# SZG-TEMPLATE-STD.net
KiCad netlist of a schematic drawn in Altium Designer
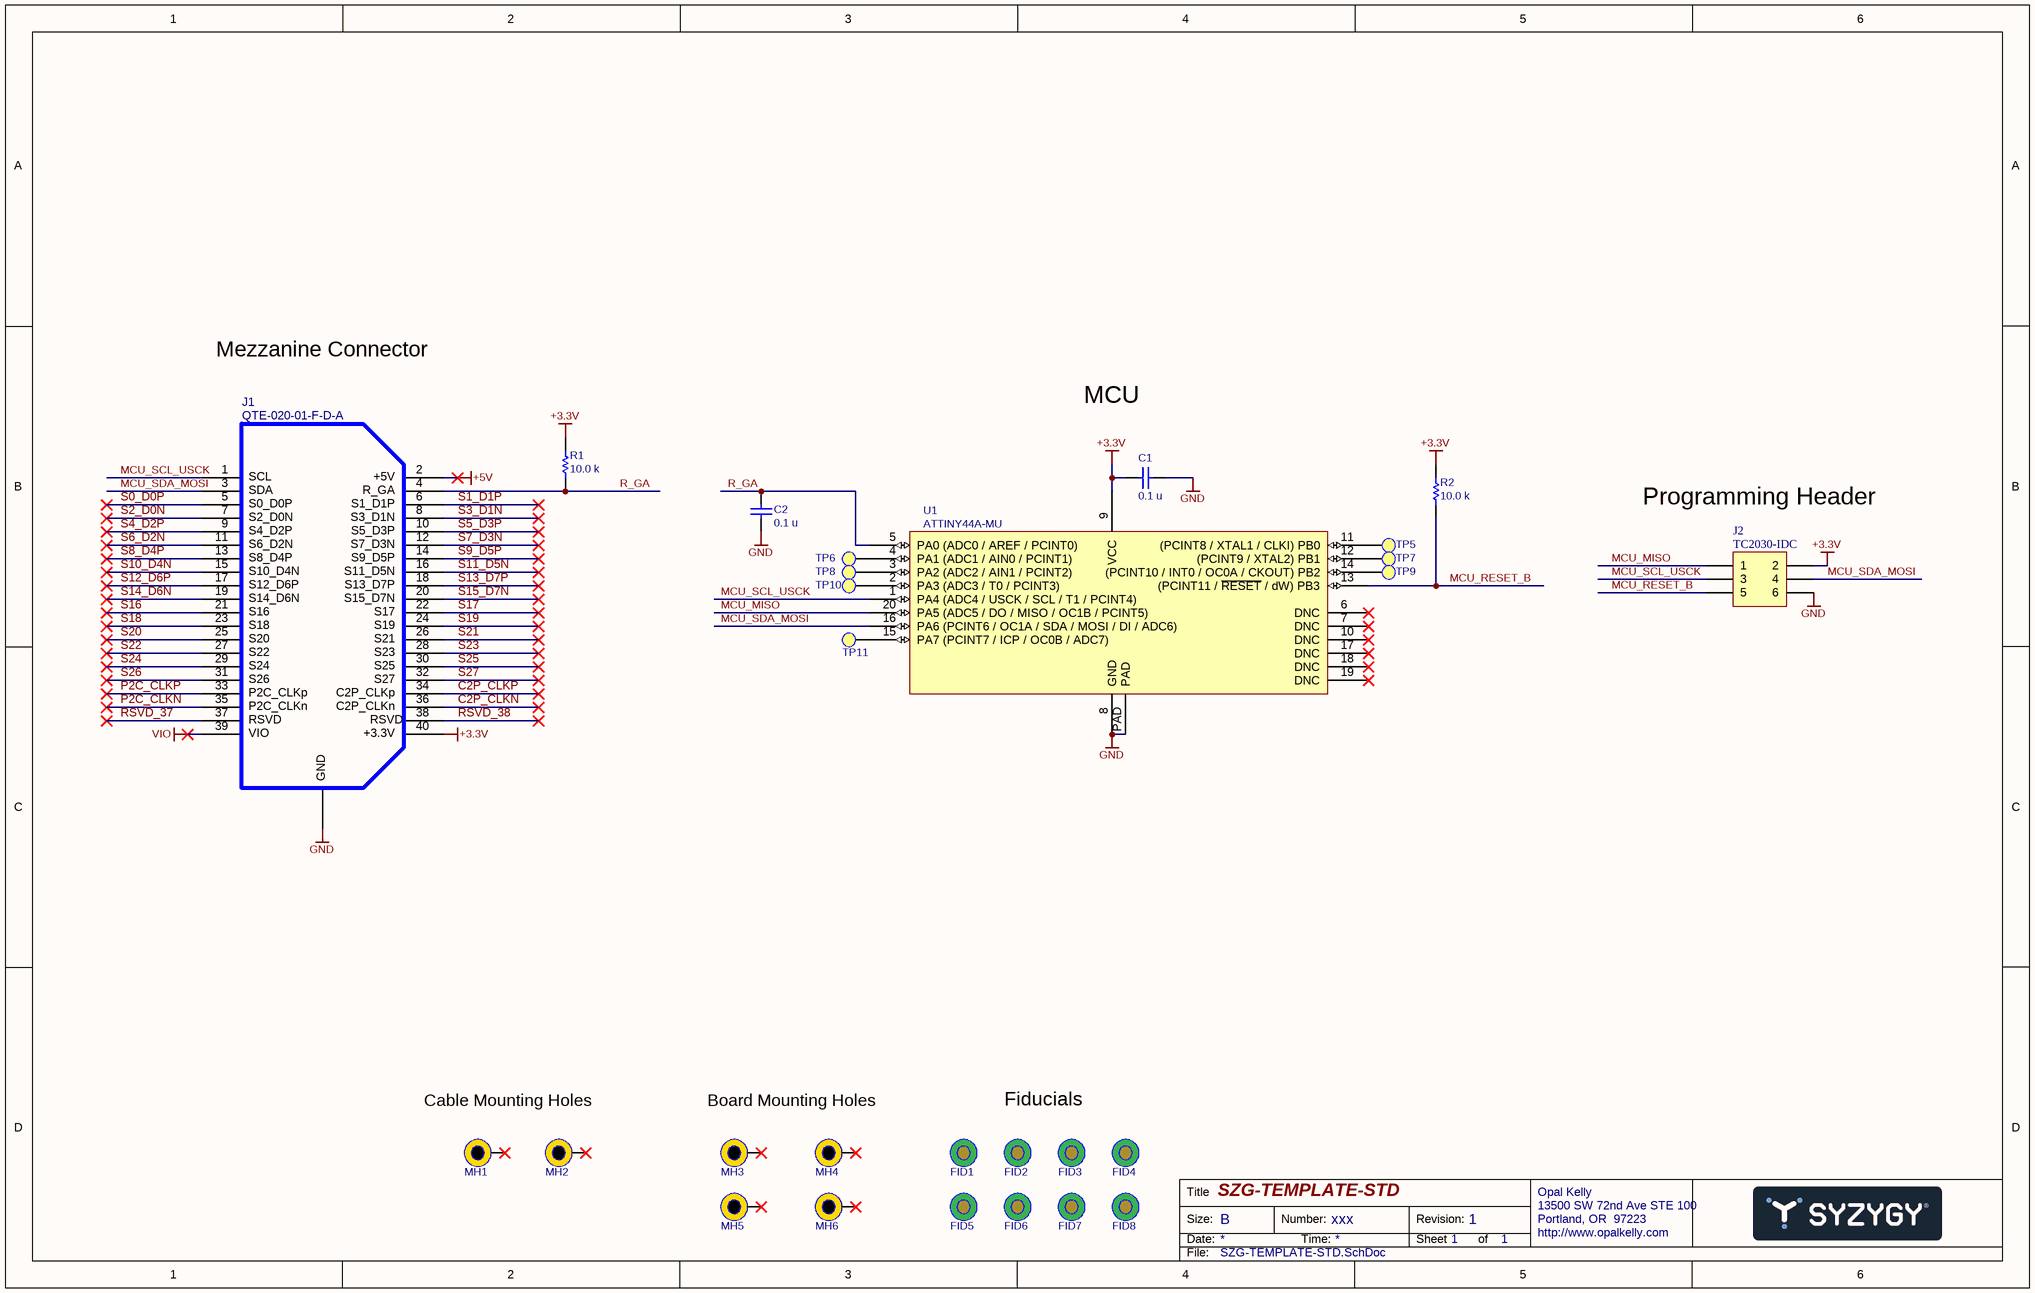
[diagram p0: SZG-TEMPLATE-STD.SchDoc]

(export (version "E")
  (design (tool "Eeschema 10.0.6"))
  (components
    (comp (ref "C1")
      (value "0.1 u")
      (footprint "CAPC1005X06N")
      (description "Ceramic capacitor")
      (fields (field (name "MANUFACTURER") "Kemet") (field (name "PARTNUMBER") "000070"))
      (libsource (lib "Aligni") (part "Capacitor"))
    )
    (comp (ref "C2")
      (value "0.1 u")
      (footprint "CAPC1005X06N")
      (description "Ceramic capacitor")
      (fields (field (name "MANUFACTURER") "Kemet") (field (name "PARTNUMBER") "000070"))
      (libsource (lib "Aligni") (part "Capacitor"))
    )
    (comp (ref "FID1")
      (value "FIDUCIAL")
      (footprint "FID1MM/2MM-SS")
      (description "PCB fiducial")
      (libsource (lib "NoBOM") (part "FIDUCIAL"))
    )
    (comp (ref "FID2")
      (value "FIDUCIAL")
      (footprint "FID1MM/2MM-SS")
      (description "PCB fiducial")
      (libsource (lib "NoBOM") (part "FIDUCIAL"))
    )
    (comp (ref "FID3")
      (value "FIDUCIAL")
      (footprint "FID1MM/2MM-SS")
      (description "PCB fiducial")
      (libsource (lib "NoBOM") (part "FIDUCIAL"))
    )
    (comp (ref "FID4")
      (value "FIDUCIAL")
      (footprint "FID1MM/2MM-SS")
      (description "PCB fiducial")
      (libsource (lib "NoBOM") (part "FIDUCIAL"))
    )
    (comp (ref "FID5")
      (value "FIDUCIAL")
      (footprint "FID1MM/2MM-SS")
      (description "PCB fiducial")
      (libsource (lib "NoBOM") (part "FIDUCIAL"))
    )
    (comp (ref "FID6")
      (value "FIDUCIAL")
      (footprint "FID1MM/2MM-SS")
      (description "PCB fiducial")
      (libsource (lib "NoBOM") (part "FIDUCIAL"))
    )
    (comp (ref "FID7")
      (value "FIDUCIAL")
      (footprint "FID1MM/2MM-SS")
      (description "PCB fiducial")
      (libsource (lib "NoBOM") (part "FIDUCIAL"))
    )
    (comp (ref "FID8")
      (value "FIDUCIAL")
      (footprint "FID1MM/2MM-SS")
      (description "PCB fiducial")
      (libsource (lib "NoBOM") (part "FIDUCIAL"))
    )
    (comp (ref "J1")
      (value "QTE-020-01-F-D-A")
      (footprint "QTE-020-01-X-D-A-L")
      (fields (field (name "PARTNUMBER") "000973") (field (name "MANUFACTURER") "Samtec"))
      (libsource (lib "Aligni") (part "QTE_QSE-020"))
    )
    (comp (ref "J2")
      (value "~")
      (footprint "TC2030-DUAL")
      (description "Tag-Connect 6-pin Plug-of-Nails spring-pin cable footprint")
      (fields
        (field (name "ALIGNIPARTNUMBER") "002062")
        (field (name "MANUFACTURER") "Tag-Connect")
        (field (name "MANUFACTURER_PN") "TC2030-IDC")
      )
      (libsource (lib "Aligni") (part "Header 3X2"))
    )
    (comp (ref "MH1")
      (value "MTG")
      (footprint "MTG-3.2/6.5-PTH")
      (description "Mounting hole")
      (libsource (lib "NoBOM") (part "MTG"))
    )
    (comp (ref "MH2")
      (value "MTG")
      (footprint "MTG-3.2/6.5-PTH")
      (description "Mounting hole")
      (libsource (lib "NoBOM") (part "MTG"))
    )
    (comp (ref "MH3")
      (value "MTG")
      (footprint "MTG-3.2/6.5-PTH")
      (description "Mounting hole")
      (libsource (lib "NoBOM") (part "MTG"))
    )
    (comp (ref "MH4")
      (value "MTG")
      (footprint "MTG-3.2/6.5-PTH")
      (description "Mounting hole")
      (libsource (lib "NoBOM") (part "MTG"))
    )
    (comp (ref "MH5")
      (value "MTG")
      (footprint "MTG-3.2/6.5-PTH")
      (description "Mounting hole")
      (libsource (lib "NoBOM") (part "MTG"))
    )
    (comp (ref "MH6")
      (value "MTG")
      (footprint "MTG-3.2/6.5-PTH")
      (description "Mounting hole")
      (libsource (lib "NoBOM") (part "MTG"))
    )
    (comp (ref "R1")
      (value "10.0 k")
      (footprint "RESC1005X06N")
      (description "Thick-film resistor")
      (fields (field (name "MANUFACTURER") "Vishay") (field (name "PARTNUMBER") "001521"))
      (libsource (lib "Aligni") (part "Resistor"))
    )
    (comp (ref "R2")
      (value "10.0 k")
      (footprint "RESC1005X06N")
      (description "Thick-film resistor")
      (fields (field (name "MANUFACTURER") "Vishay") (field (name "PARTNUMBER") "001521"))
      (libsource (lib "Aligni") (part "Resistor"))
    )
    (comp (ref "TP5")
      (value "TESTPOINT-SMD20")
      (footprint "TP-SMD20")
      (description "Test point, surface-mount, 20mil")
      (libsource (lib "NoBOM") (part "TESTPOINT-SMD20"))
    )
    (comp (ref "TP6")
      (value "TESTPOINT-SMD20")
      (footprint "TP-SMD20")
      (description "Test point, surface-mount, 20mil")
      (libsource (lib "NoBOM") (part "TESTPOINT-SMD20"))
    )
    (comp (ref "TP7")
      (value "TESTPOINT-SMD20")
      (footprint "TP-SMD20")
      (description "Test point, surface-mount, 20mil")
      (libsource (lib "NoBOM") (part "TESTPOINT-SMD20"))
    )
    (comp (ref "TP8")
      (value "TESTPOINT-SMD20")
      (footprint "TP-SMD20")
      (description "Test point, surface-mount, 20mil")
      (libsource (lib "NoBOM") (part "TESTPOINT-SMD20"))
    )
    (comp (ref "TP9")
      (value "TESTPOINT-SMD20")
      (footprint "TP-SMD20")
      (description "Test point, surface-mount, 20mil")
      (libsource (lib "NoBOM") (part "TESTPOINT-SMD20"))
    )
    (comp (ref "TP10")
      (value "TESTPOINT-SMD20")
      (footprint "TP-SMD20")
      (description "Test point, surface-mount, 20mil")
      (libsource (lib "NoBOM") (part "TESTPOINT-SMD20"))
    )
    (comp (ref "TP11")
      (value "TESTPOINT-SMD20")
      (footprint "TP-SMD20")
      (description "Test point, surface-mount, 20mil")
      (libsource (lib "NoBOM") (part "TESTPOINT-SMD20"))
    )
    (comp (ref "U1")
      (value "ATTINY44A-MU")
      (footprint "QFN-EP-20")
      (description "8-bit MCU, 4 KB flash, 256 bytes EEPROM")
      (fields (field (name "MANUFACTURER") "Microchip") (field (name "PARTNUMBER") "001552"))
      (libsource (lib "Aligni") (part "ATTINYx4A-MU"))
    )
  )
  (nets
    (net (code "1") (name "+3.3V") (class "Default")
      (node (ref "C1") (pin "2") (pinfunction "2_2") (pintype "passive"))
      (node (ref "J1") (pin "40") (pinfunction "40_40") (pintype "passive"))
      (node (ref "J2") (pin "2") (pinfunction "2_2") (pintype "passive"))
      (node (ref "R1") (pin "2") (pinfunction "2_2") (pintype "passive"))
      (node (ref "R2") (pin "2") (pinfunction "2_2") (pintype "passive"))
      (node (ref "U1") (pin "9") (pinfunction "VCC_9") (pintype "power_in"))
    )
    (net (code "2") (name "+5V") (class "Default")
      (node (ref "J1") (pin "2") (pinfunction "2_2") (pintype "passive"))
    )
    (net (code "3") (name "/C2P_CLKN") (class "Default")
      (node (ref "J1") (pin "36") (pinfunction "36_36") (pintype "passive+no_connect"))
    )
    (net (code "4") (name "/C2P_CLKP") (class "Default")
      (node (ref "J1") (pin "34") (pinfunction "34_34") (pintype "passive+no_connect"))
    )
    (net (code "5") (name "/MCU_MISO") (class "Default")
      (node (ref "J2") (pin "1") (pinfunction "1_1") (pintype "passive"))
      (node (ref "U1") (pin "20") (pinfunction "PA5_(ADC5_/_DO_/_MISO_/_OC1B_/_PCINT5)_20") (pintype "bidirectional"))
    )
    (net (code "6") (name "/MCU_RESET_B") (class "Default")
      (node (ref "J2") (pin "5") (pinfunction "5_5") (pintype "passive"))
      (node (ref "R2") (pin "1") (pinfunction "1_1") (pintype "passive"))
      (node (ref "U1") (pin "13") (pinfunction "(PCINT11_/_~{RESET}_/_dW)_PB3_13") (pintype "bidirectional"))
    )
    (net (code "7") (name "/MCU_SCL_USCK") (class "Default")
      (node (ref "J1") (pin "1") (pinfunction "1_1") (pintype "passive"))
      (node (ref "J2") (pin "3") (pinfunction "3_3") (pintype "passive"))
      (node (ref "U1") (pin "1") (pinfunction "PA4_(ADC4_/_USCK_/_SCL_/_T1_/_PCINT4)_1") (pintype "bidirectional"))
    )
    (net (code "8") (name "/MCU_SDA_MOSI") (class "Default")
      (node (ref "J1") (pin "3") (pinfunction "3_3") (pintype "passive"))
      (node (ref "J2") (pin "4") (pinfunction "4_4") (pintype "passive"))
      (node (ref "U1") (pin "16") (pinfunction "PA6_(PCINT6_/_OC1A_/_SDA_/_MOSI_/_DI_/_ADC6)_16") (pintype "bidirectional"))
    )
    (net (code "9") (name "/P2C_CLKN") (class "Default")
      (node (ref "J1") (pin "35") (pinfunction "35_35") (pintype "passive+no_connect"))
    )
    (net (code "10") (name "/P2C_CLKP") (class "Default")
      (node (ref "J1") (pin "33") (pinfunction "33_33") (pintype "passive+no_connect"))
    )
    (net (code "11") (name "/RSVD_37") (class "Default")
      (node (ref "J1") (pin "37") (pinfunction "37_37") (pintype "passive+no_connect"))
    )
    (net (code "12") (name "/RSVD_38") (class "Default")
      (node (ref "J1") (pin "38") (pinfunction "38_38") (pintype "passive+no_connect"))
    )
    (net (code "13") (name "/R_GA") (class "Default")
      (node (ref "C2") (pin "2") (pinfunction "2_2") (pintype "passive"))
      (node (ref "J1") (pin "4") (pinfunction "4_4") (pintype "passive"))
      (node (ref "R1") (pin "1") (pinfunction "1_1") (pintype "passive"))
      (node (ref "U1") (pin "5") (pinfunction "PA0_(ADC0_/_AREF_/_PCINT0)_5") (pintype "bidirectional"))
    )
    (net (code "14") (name "/S0_D0P") (class "Default")
      (node (ref "J1") (pin "5") (pinfunction "5_5") (pintype "passive+no_connect"))
    )
    (net (code "15") (name "/S1_D1P") (class "Default")
      (node (ref "J1") (pin "6") (pinfunction "6_6") (pintype "passive+no_connect"))
    )
    (net (code "16") (name "/S2_D0N") (class "Default")
      (node (ref "J1") (pin "7") (pinfunction "7_7") (pintype "passive+no_connect"))
    )
    (net (code "17") (name "/S3_D1N") (class "Default")
      (node (ref "J1") (pin "8") (pinfunction "8_8") (pintype "passive+no_connect"))
    )
    (net (code "18") (name "/S4_D2P") (class "Default")
      (node (ref "J1") (pin "9") (pinfunction "9_9") (pintype "passive+no_connect"))
    )
    (net (code "19") (name "/S5_D3P") (class "Default")
      (node (ref "J1") (pin "10") (pinfunction "10_10") (pintype "passive+no_connect"))
    )
    (net (code "20") (name "/S6_D2N") (class "Default")
      (node (ref "J1") (pin "11") (pinfunction "11_11") (pintype "passive+no_connect"))
    )
    (net (code "21") (name "/S7_D3N") (class "Default")
      (node (ref "J1") (pin "12") (pinfunction "12_12") (pintype "passive+no_connect"))
    )
    (net (code "22") (name "/S8_D4P") (class "Default")
      (node (ref "J1") (pin "13") (pinfunction "13_13") (pintype "passive+no_connect"))
    )
    (net (code "23") (name "/S9_D5P") (class "Default")
      (node (ref "J1") (pin "14") (pinfunction "14_14") (pintype "passive+no_connect"))
    )
    (net (code "24") (name "/S10_D4N") (class "Default")
      (node (ref "J1") (pin "15") (pinfunction "15_15") (pintype "passive+no_connect"))
    )
    (net (code "25") (name "/S11_D5N") (class "Default")
      (node (ref "J1") (pin "16") (pinfunction "16_16") (pintype "passive+no_connect"))
    )
    (net (code "26") (name "/S12_D6P") (class "Default")
      (node (ref "J1") (pin "17") (pinfunction "17_17") (pintype "passive+no_connect"))
    )
    (net (code "27") (name "/S13_D7P") (class "Default")
      (node (ref "J1") (pin "18") (pinfunction "18_18") (pintype "passive+no_connect"))
    )
    (net (code "28") (name "/S14_D6N") (class "Default")
      (node (ref "J1") (pin "19") (pinfunction "19_19") (pintype "passive+no_connect"))
    )
    (net (code "29") (name "/S15_D7N") (class "Default")
      (node (ref "J1") (pin "20") (pinfunction "20_20") (pintype "passive+no_connect"))
    )
    (net (code "30") (name "/S16") (class "Default")
      (node (ref "J1") (pin "21") (pinfunction "21_21") (pintype "passive+no_connect"))
    )
    (net (code "31") (name "/S17") (class "Default")
      (node (ref "J1") (pin "22") (pinfunction "22_22") (pintype "passive+no_connect"))
    )
    (net (code "32") (name "/S18") (class "Default")
      (node (ref "J1") (pin "23") (pinfunction "23_23") (pintype "passive+no_connect"))
    )
    (net (code "33") (name "/S19") (class "Default")
      (node (ref "J1") (pin "24") (pinfunction "24_24") (pintype "passive+no_connect"))
    )
    (net (code "34") (name "/S20") (class "Default")
      (node (ref "J1") (pin "25") (pinfunction "25_25") (pintype "passive+no_connect"))
    )
    (net (code "35") (name "/S21") (class "Default")
      (node (ref "J1") (pin "26") (pinfunction "26_26") (pintype "passive+no_connect"))
    )
    (net (code "36") (name "/S22") (class "Default")
      (node (ref "J1") (pin "27") (pinfunction "27_27") (pintype "passive+no_connect"))
    )
    (net (code "37") (name "/S23") (class "Default")
      (node (ref "J1") (pin "28") (pinfunction "28_28") (pintype "passive+no_connect"))
    )
    (net (code "38") (name "/S24") (class "Default")
      (node (ref "J1") (pin "29") (pinfunction "29_29") (pintype "passive+no_connect"))
    )
    (net (code "39") (name "/S25") (class "Default")
      (node (ref "J1") (pin "30") (pinfunction "30_30") (pintype "passive+no_connect"))
    )
    (net (code "40") (name "/S26") (class "Default")
      (node (ref "J1") (pin "31") (pinfunction "31_31") (pintype "passive+no_connect"))
    )
    (net (code "41") (name "/S27") (class "Default")
      (node (ref "J1") (pin "32") (pinfunction "32_32") (pintype "passive+no_connect"))
    )
    (net (code "42") (name "GND") (class "Default")
      (node (ref "C1") (pin "1") (pinfunction "1_1") (pintype "passive"))
      (node (ref "C2") (pin "1") (pinfunction "1_1") (pintype "passive"))
      (node (ref "J1") (pin "0") (pinfunction "0_0") (pintype "passive"))
      (node (ref "J2") (pin "6") (pinfunction "6_6") (pintype "passive"))
      (node (ref "U1") (pin "8") (pinfunction "GND_8") (pintype "power_in"))
      (node (ref "U1") (pin "PAD") (pinfunction "PAD_PAD") (pintype "power_in"))
    )
    (net (code "43") (name "Net-(TP5-PIN)") (class "Default")
      (node (ref "TP5") (pin "1") (pinfunction "PIN_1") (pintype "passive"))
      (node (ref "U1") (pin "11") (pinfunction "(PCINT8_/_XTAL1_/_CLKI)_PB0_11") (pintype "bidirectional"))
    )
    (net (code "44") (name "Net-(TP6-PIN)") (class "Default")
      (node (ref "TP6") (pin "1") (pinfunction "PIN_1") (pintype "passive"))
      (node (ref "U1") (pin "4") (pinfunction "PA1_(ADC1_/_AIN0_/_PCINT1)_4") (pintype "bidirectional"))
    )
    (net (code "45") (name "Net-(TP7-PIN)") (class "Default")
      (node (ref "TP7") (pin "1") (pinfunction "PIN_1") (pintype "passive"))
      (node (ref "U1") (pin "12") (pinfunction "(PCINT9_/_XTAL2)_PB1_12") (pintype "bidirectional"))
    )
    (net (code "46") (name "Net-(TP8-PIN)") (class "Default")
      (node (ref "TP8") (pin "1") (pinfunction "PIN_1") (pintype "passive"))
      (node (ref "U1") (pin "3") (pinfunction "PA2_(ADC2_/_AIN1_/_PCINT2)_3") (pintype "bidirectional"))
    )
    (net (code "47") (name "Net-(TP9-PIN)") (class "Default")
      (node (ref "TP9") (pin "1") (pinfunction "PIN_1") (pintype "passive"))
      (node (ref "U1") (pin "14") (pinfunction "(PCINT10_/_INT0_/_OC0A_/_CKOUT)_PB2_14") (pintype "bidirectional"))
    )
    (net (code "48") (name "Net-(TP10-PIN)") (class "Default")
      (node (ref "TP10") (pin "1") (pinfunction "PIN_1") (pintype "passive"))
      (node (ref "U1") (pin "2") (pinfunction "PA3_(ADC3_/_T0_/_PCINT3)_2") (pintype "bidirectional"))
    )
    (net (code "49") (name "Net-(TP11-PIN)") (class "Default")
      (node (ref "TP11") (pin "1") (pinfunction "PIN_1") (pintype "passive"))
      (node (ref "U1") (pin "15") (pinfunction "PA7_(PCINT7_/_ICP_/_OC0B_/_ADC7)_15") (pintype "bidirectional"))
    )
    (net (code "50") (name "VIO") (class "Default")
      (node (ref "J1") (pin "39") (pinfunction "39_39") (pintype "passive"))
    )
    (net (code "51") (name "unconnected-(MH1-Pad1)") (class "Default")
      (node (ref "MH1") (pin "1") (pinfunction "1_1") (pintype "passive+no_connect"))
    )
    (net (code "52") (name "unconnected-(MH2-Pad1)") (class "Default")
      (node (ref "MH2") (pin "1") (pinfunction "1_1") (pintype "passive+no_connect"))
    )
    (net (code "53") (name "unconnected-(MH3-Pad1)") (class "Default")
      (node (ref "MH3") (pin "1") (pinfunction "1_1") (pintype "passive+no_connect"))
    )
    (net (code "54") (name "unconnected-(MH4-Pad1)") (class "Default")
      (node (ref "MH4") (pin "1") (pinfunction "1_1") (pintype "passive+no_connect"))
    )
    (net (code "55") (name "unconnected-(MH5-Pad1)") (class "Default")
      (node (ref "MH5") (pin "1") (pinfunction "1_1") (pintype "passive+no_connect"))
    )
    (net (code "56") (name "unconnected-(MH6-Pad1)") (class "Default")
      (node (ref "MH6") (pin "1") (pinfunction "1_1") (pintype "passive+no_connect"))
    )
    (net (code "57") (name "unconnected-(U1-DNC-Pad6)") (class "Default")
      (node (ref "U1") (pin "6") (pinfunction "DNC_6") (pintype "passive+no_connect"))
    )
    (net (code "58") (name "unconnected-(U1-DNC-Pad7)") (class "Default")
      (node (ref "U1") (pin "7") (pinfunction "DNC_7") (pintype "passive+no_connect"))
    )
    (net (code "59") (name "unconnected-(U1-DNC-Pad10)") (class "Default")
      (node (ref "U1") (pin "10") (pinfunction "DNC_10") (pintype "passive+no_connect"))
    )
    (net (code "60") (name "unconnected-(U1-DNC-Pad17)") (class "Default")
      (node (ref "U1") (pin "17") (pinfunction "DNC_17") (pintype "passive+no_connect"))
    )
    (net (code "61") (name "unconnected-(U1-DNC-Pad18)") (class "Default")
      (node (ref "U1") (pin "18") (pinfunction "DNC_18") (pintype "passive+no_connect"))
    )
    (net (code "62") (name "unconnected-(U1-DNC-Pad19)") (class "Default")
      (node (ref "U1") (pin "19") (pinfunction "DNC_19") (pintype "passive+no_connect"))
    )
  )
)
